# main.net
KiCad netlist of a schematic drawn in EAGLE
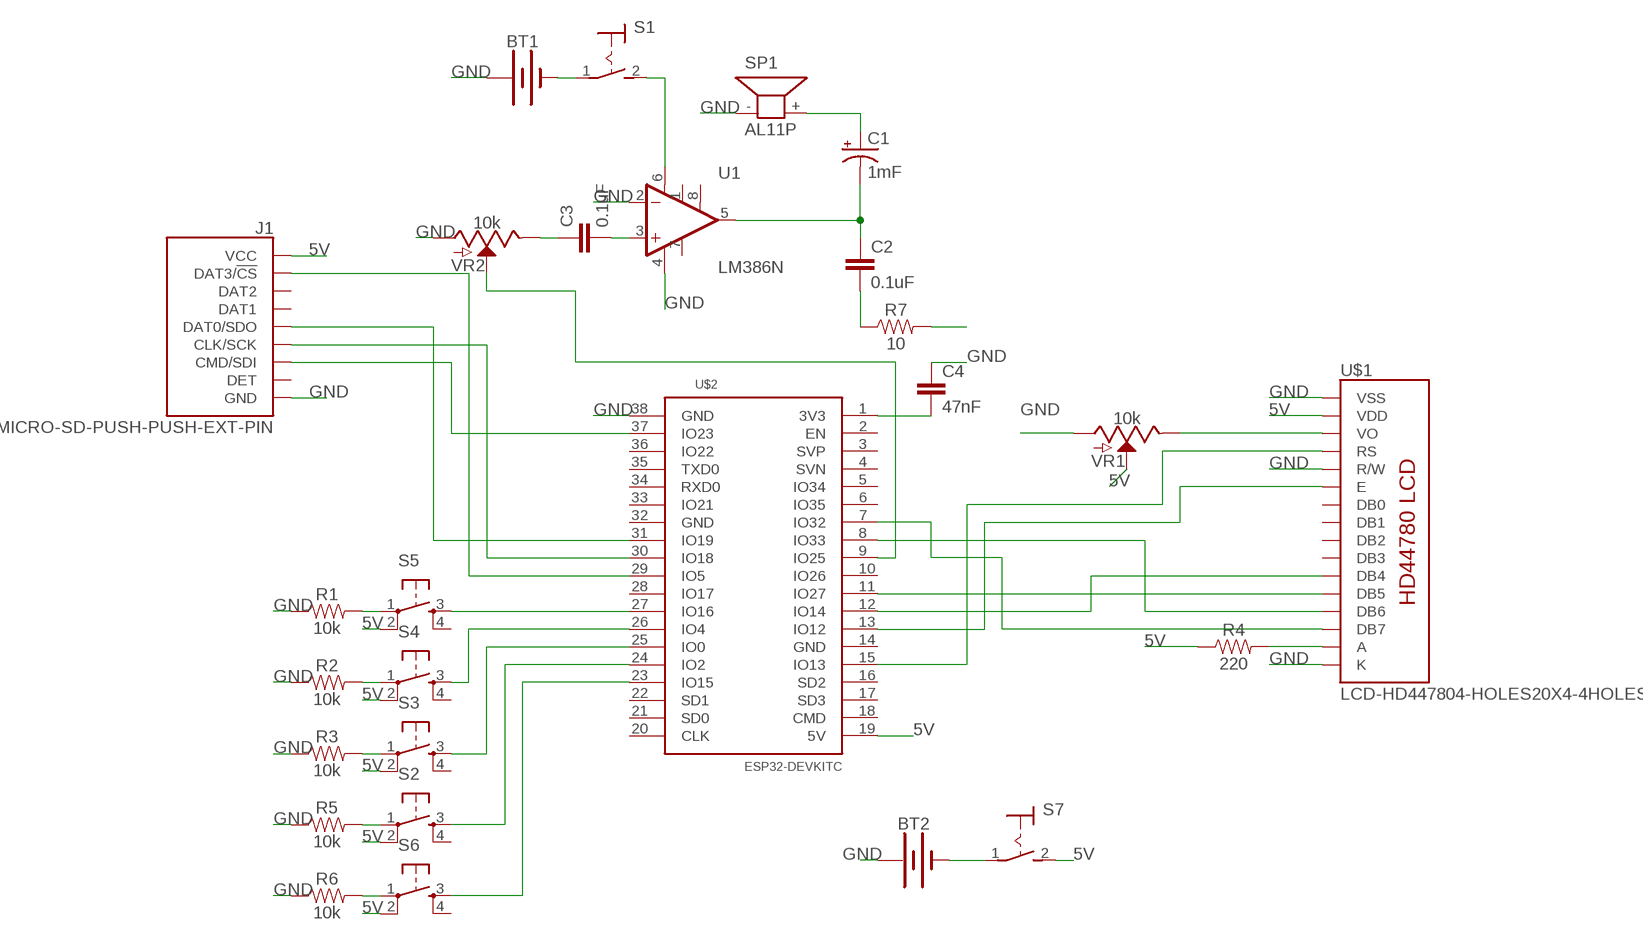
[diagram p0: schematic, sheet 1]

(export (version "E")
  (design (tool "Eeschema 10.0.6"))
  (components
    (comp (ref "BT1")
      (value "BATTERY-9V")
      (footprint "eagle-import:BATTCON_9V")
      (libsource (lib "eagle-import") (part "BATTERY-9V"))
    )
    (comp (ref "BT2")
      (value "BATTERY-9V")
      (footprint "eagle-import:BATTCON_9V")
      (libsource (lib "eagle-import") (part "BATTERY-9V"))
    )
    (comp (ref "C1")
      (value "1mF")
      (footprint "eagle-import:CPOL-RADIAL-5MM-10MM")
      (libsource (lib "eagle-import") (part "1000UF-RADIAL-5MM-25V-20%"))
    )
    (comp (ref "C2")
      (value "0.1uF")
      (footprint "eagle-import:CAP-PTH-SMALL-KIT")
      (libsource (lib "eagle-import") (part "0.1UF-KIT-EZ-50V-20%"))
    )
    (comp (ref "C3")
      (value "0.1uF")
      (footprint "eagle-import:CAP-PTH-SMALL-KIT")
      (libsource (lib "eagle-import") (part "0.1UF-KIT-EZ-50V-20%"))
    )
    (comp (ref "C4")
      (value "47nF")
      (footprint "eagle-import:0603")
      (libsource (lib "eagle-import") (part "47NF-0603-25V-5%"))
    )
    (comp (ref "J1")
      (value "MICRO-SD-PUSH-PUSH-EXT-PIN")
      (footprint "eagle-import:MICROSD-EXTERNALPIN")
      (libsource (lib "eagle-import") (part "MICRO-SD-PUSH-PUSH-EXT-PIN"))
    )
    (comp (ref "R1")
      (value "10k")
      (footprint "eagle-import:AXIAL-0.3")
      (libsource (lib "eagle-import") (part "10KOHM-HORIZ-1/4W-1%"))
    )
    (comp (ref "R2")
      (value "10k")
      (footprint "eagle-import:AXIAL-0.3")
      (libsource (lib "eagle-import") (part "10KOHM-HORIZ-1/4W-1%"))
    )
    (comp (ref "R3")
      (value "10k")
      (footprint "eagle-import:AXIAL-0.3")
      (libsource (lib "eagle-import") (part "10KOHM-HORIZ-1/4W-1%"))
    )
    (comp (ref "R4")
      (value "220")
      (footprint "eagle-import:0603")
      (libsource (lib "eagle-import") (part "220OHM-0603-1/10W-1%"))
    )
    (comp (ref "R5")
      (value "10k")
      (footprint "eagle-import:AXIAL-0.3")
      (libsource (lib "eagle-import") (part "10KOHM-HORIZ-1/4W-1%"))
    )
    (comp (ref "R6")
      (value "10k")
      (footprint "eagle-import:AXIAL-0.3")
      (libsource (lib "eagle-import") (part "10KOHM-HORIZ-1/4W-1%"))
    )
    (comp (ref "R7")
      (value "10")
      (footprint "eagle-import:AXIAL-0.3")
      (libsource (lib "eagle-import") (part "10OHM-HORIZ-1/4W-1%"))
    )
    (comp (ref "S1")
      (value "MS243")
      (footprint "eagle-import:MS243")
      (libsource (lib "eagle-import") (part "MS243"))
    )
    (comp (ref "S2")
      (value "TAC_SWITCHPTH")
      (footprint "eagle-import:TACTILE-PTH")
      (fields (field (name "SPICEPREFIX") "S"))
      (libsource (lib "eagle-import") (part "TAC_SWITCHPTH"))
    )
    (comp (ref "S3")
      (value "TAC_SWITCHPTH")
      (footprint "eagle-import:TACTILE-PTH")
      (fields (field (name "SPICEPREFIX") "S"))
      (libsource (lib "eagle-import") (part "TAC_SWITCHPTH"))
    )
    (comp (ref "S4")
      (value "TAC_SWITCHPTH")
      (footprint "eagle-import:TACTILE-PTH")
      (fields (field (name "SPICEPREFIX") "S"))
      (libsource (lib "eagle-import") (part "TAC_SWITCHPTH"))
    )
    (comp (ref "S5")
      (value "TAC_SWITCHPTH")
      (footprint "eagle-import:TACTILE-PTH")
      (fields (field (name "SPICEPREFIX") "S"))
      (libsource (lib "eagle-import") (part "TAC_SWITCHPTH"))
    )
    (comp (ref "S6")
      (value "TAC_SWITCHPTH")
      (footprint "eagle-import:TACTILE-PTH")
      (fields (field (name "SPICEPREFIX") "S"))
      (libsource (lib "eagle-import") (part "TAC_SWITCHPTH"))
    )
    (comp (ref "S7")
      (value "MS243")
      (footprint "eagle-import:MS243")
      (libsource (lib "eagle-import") (part "MS243"))
    )
    (comp (ref "SP1")
      (value "AL11P")
      (footprint "eagle-import:AL11P")
      (libsource (lib "eagle-import") (part "AL11P"))
    )
    (comp (ref "U$1")
      (value "LCD-HD447804-HOLES20X4-4HOLES")
      (footprint "eagle-import:LCD-20X4-4HOLES")
      (libsource (lib "eagle-import") (part "LCD-HD4478020X4-4HOLES4-HOLES"))
    )
    (comp (ref "U$2")
      (value "ESP32DEVKITC")
      (footprint "eagle-import:ESP32-DEVKITC")
      (libsource (lib "eagle-import") (part "ESP32DEVKITC"))
    )
    (comp (ref "U1")
      (value "LM386N")
      (footprint "eagle-import:DIP08")
      (libsource (lib "eagle-import") (part "LM386"))
    )
    (comp (ref "VR1")
      (value "10k")
      (footprint "eagle-import:SLIDER-XLARGE")
      (libsource (lib "eagle-import") (part "POTENTIOMETER_SLIDE-60MM-1/2W-20%"))
    )
    (comp (ref "VR2")
      (value "10k")
      (footprint "eagle-import:SLIDER-XLARGE")
      (libsource (lib "eagle-import") (part "POTENTIOMETER_SLIDE-60MM-1/2W-20%"))
    )
  )
  (nets
    (net (code "1") (name "/5V") (class "Default")
      (node (ref "J1") (pin "4") (pinfunction "VCC_4") (pintype "bidirectional"))
      (node (ref "R4") (pin "1") (pinfunction "1_1") (pintype "passive"))
      (node (ref "S2") (pin "2") (pinfunction "2_2") (pintype "passive"))
      (node (ref "S3") (pin "2") (pinfunction "2_2") (pintype "passive"))
      (node (ref "S4") (pin "2") (pinfunction "2_2") (pintype "passive"))
      (node (ref "S5") (pin "2") (pinfunction "2_2") (pintype "passive"))
      (node (ref "S6") (pin "2") (pinfunction "2_2") (pintype "passive"))
      (node (ref "S7") (pin "2") (pinfunction "S_2") (pintype "passive"))
      (node (ref "U$1") (pin "P$2") (pinfunction "VDD_P$2") (pintype "power_in"))
      (node (ref "U$2") (pin "19") (pinfunction "5V_19") (pintype "bidirectional"))
      (node (ref "VR1") (pin "2A") (pinfunction "S_2A") (pintype "passive"))
    )
    (net (code "2") (name "/GND") (class "Default")
      (node (ref "BT1") (pin "+") (pinfunction "+_+") (pintype "power_in"))
      (node (ref "BT2") (pin "+") (pinfunction "+_+") (pintype "power_in"))
      (node (ref "C4") (pin "1") (pinfunction "1_1") (pintype "passive"))
      (node (ref "J1") (pin "10") (pinfunction "GND_10") (pintype "bidirectional"))
      (node (ref "J1") (pin "11") (pinfunction "GND_11") (pintype "bidirectional"))
      (node (ref "J1") (pin "12") (pinfunction "GND_12") (pintype "bidirectional"))
      (node (ref "J1") (pin "13") (pinfunction "GND_13") (pintype "bidirectional"))
      (node (ref "J1") (pin "6") (pinfunction "GND_6") (pintype "bidirectional"))
      (node (ref "R1") (pin "P$1") (pinfunction "1_P$1") (pintype "passive"))
      (node (ref "R2") (pin "P$1") (pinfunction "1_P$1") (pintype "passive"))
      (node (ref "R3") (pin "P$1") (pinfunction "1_P$1") (pintype "passive"))
      (node (ref "R5") (pin "P$1") (pinfunction "1_P$1") (pintype "passive"))
      (node (ref "R6") (pin "P$1") (pinfunction "1_P$1") (pintype "passive"))
      (node (ref "SP1") (pin "-") (pinfunction "1_-") (pintype "passive"))
      (node (ref "U$1") (pin "P$1") (pinfunction "VSS_P$1") (pintype "power_in"))
      (node (ref "U$1") (pin "P$16") (pinfunction "K_P$16") (pintype "power_in"))
      (node (ref "U$1") (pin "P$5") (pinfunction "R/W_P$5") (pintype "input"))
      (node (ref "U$2") (pin "38") (pinfunction "GND_38") (pintype "bidirectional"))
      (node (ref "U1") (pin "2") (pinfunction "-IN_2") (pintype "input"))
      (node (ref "U1") (pin "4") (pinfunction "V-_4") (pintype "power_in"))
      (node (ref "VR1") (pin "3") (pinfunction "A_3") (pintype "passive"))
      (node (ref "VR2") (pin "3") (pinfunction "A_3") (pintype "passive"))
    )
    (net (code "3") (name "Net-(J1-CLK{slash}SCK)") (class "Default")
      (node (ref "J1") (pin "5") (pinfunction "CLK/SCK_5") (pintype "bidirectional"))
      (node (ref "U$2") (pin "30") (pinfunction "IO18_30") (pintype "bidirectional"))
    )
    (net (code "4") (name "Net-(J1-CMD{slash}SDI)") (class "Default")
      (node (ref "J1") (pin "3") (pinfunction "CMD/SDI_3") (pintype "bidirectional"))
      (node (ref "U$2") (pin "37") (pinfunction "IO23_37") (pintype "bidirectional"))
    )
    (net (code "5") (name "Net-(J1-DAT0{slash}SDO)") (class "Default")
      (node (ref "J1") (pin "7") (pinfunction "DAT0/SDO_7") (pintype "bidirectional"))
      (node (ref "U$2") (pin "31") (pinfunction "IO19_31") (pintype "bidirectional"))
    )
    (net (code "6") (name "Net-(J1-DAT3{slash}~{CS})") (class "Default")
      (node (ref "J1") (pin "2") (pinfunction "DAT3/~{CS}_2") (pintype "bidirectional"))
      (node (ref "U$2") (pin "29") (pinfunction "IO5_29") (pintype "bidirectional"))
    )
    (net (code "7") (name "Net-(R1-2)") (class "Default")
      (node (ref "R1") (pin "P$2") (pinfunction "2_P$2") (pintype "passive"))
      (node (ref "S5") (pin "1") (pinfunction "1_1") (pintype "passive"))
    )
    (net (code "8") (name "Net-(R2-2)") (class "Default")
      (node (ref "R2") (pin "P$2") (pinfunction "2_P$2") (pintype "passive"))
      (node (ref "S4") (pin "1") (pinfunction "1_1") (pintype "passive"))
    )
    (net (code "9") (name "Net-(R3-2)") (class "Default")
      (node (ref "R3") (pin "P$2") (pinfunction "2_P$2") (pintype "passive"))
      (node (ref "S3") (pin "1") (pinfunction "1_1") (pintype "passive"))
    )
    (net (code "10") (name "Net-(R5-2)") (class "Default")
      (node (ref "R5") (pin "P$2") (pinfunction "2_P$2") (pintype "passive"))
      (node (ref "S2") (pin "1") (pinfunction "1_1") (pintype "passive"))
    )
    (net (code "11") (name "Net-(R6-2)") (class "Default")
      (node (ref "R6") (pin "P$2") (pinfunction "2_P$2") (pintype "passive"))
      (node (ref "S6") (pin "1") (pinfunction "1_1") (pintype "passive"))
    )
    (net (code "12") (name "Net-(R7-1)") (class "Default")
      (node (ref "C2") (pin "2") (pinfunction "2_2") (pintype "passive"))
      (node (ref "R7") (pin "P$1") (pinfunction "1_P$1") (pintype "passive"))
    )
    (net (code "13") (name "Net-(S1-P)") (class "Default")
      (node (ref "BT1") (pin "-") (pinfunction "-_-") (pintype "power_in"))
      (node (ref "S1") (pin "1") (pinfunction "P_1") (pintype "passive"))
    )
    (net (code "14") (name "Net-(S1-S)") (class "Default")
      (node (ref "S1") (pin "2") (pinfunction "S_2") (pintype "passive"))
      (node (ref "U1") (pin "6") (pinfunction "V+_6") (pintype "power_in"))
    )
    (net (code "15") (name "Net-(S7-P)") (class "Default")
      (node (ref "BT2") (pin "-") (pinfunction "-_-") (pintype "power_in"))
      (node (ref "S7") (pin "1") (pinfunction "P_1") (pintype "passive"))
    )
    (net (code "16") (name "Net-(SP1-2)") (class "Default")
      (node (ref "C1") (pin "+") (pinfunction "+_+") (pintype "passive"))
      (node (ref "SP1") (pin "+") (pinfunction "2_+") (pintype "passive"))
    )
    (net (code "17") (name "Net-(U$1-A)") (class "Default")
      (node (ref "R4") (pin "2") (pinfunction "2_2") (pintype "passive"))
      (node (ref "U$1") (pin "P$15") (pinfunction "A_P$15") (pintype "power_in"))
    )
    (net (code "18") (name "Net-(U$1-DB4)") (class "Default")
      (node (ref "U$1") (pin "P$11") (pinfunction "DB4_P$11") (pintype "bidirectional"))
      (node (ref "U$2") (pin "12") (pinfunction "IO14_12") (pintype "bidirectional"))
    )
    (net (code "19") (name "Net-(U$1-DB5)") (class "Default")
      (node (ref "U$1") (pin "P$12") (pinfunction "DB5_P$12") (pintype "bidirectional"))
      (node (ref "U$2") (pin "11") (pinfunction "IO27_11") (pintype "bidirectional"))
    )
    (net (code "20") (name "Net-(U$1-DB6)") (class "Default")
      (node (ref "U$1") (pin "P$13") (pinfunction "DB6_P$13") (pintype "bidirectional"))
      (node (ref "U$2") (pin "8") (pinfunction "IO33_8") (pintype "bidirectional"))
    )
    (net (code "21") (name "Net-(U$1-DB7)") (class "Default")
      (node (ref "U$1") (pin "P$14") (pinfunction "DB7_P$14") (pintype "bidirectional"))
      (node (ref "U$2") (pin "7") (pinfunction "IO32_7") (pintype "bidirectional"))
    )
    (net (code "22") (name "Net-(U$1-E)") (class "Default")
      (node (ref "U$1") (pin "P$6") (pinfunction "E_P$6") (pintype "input"))
      (node (ref "U$2") (pin "13") (pinfunction "IO12_13") (pintype "bidirectional"))
    )
    (net (code "23") (name "Net-(U$1-RS)") (class "Default")
      (node (ref "U$1") (pin "P$4") (pinfunction "RS_P$4") (pintype "input"))
      (node (ref "U$2") (pin "15") (pinfunction "IO13_15") (pintype "bidirectional"))
    )
    (net (code "24") (name "Net-(U$1-VO)") (class "Default")
      (node (ref "U$1") (pin "P$3") (pinfunction "VO_P$3") (pintype "bidirectional"))
      (node (ref "VR1") (pin "1") (pinfunction "E_1") (pintype "passive"))
    )
    (net (code "25") (name "Net-(U$2-3V3)") (class "Default")
      (node (ref "C4") (pin "2") (pinfunction "2_2") (pintype "passive"))
      (node (ref "U$2") (pin "1") (pinfunction "3V3_1") (pintype "bidirectional"))
    )
    (net (code "26") (name "Net-(U$2-IO0)") (class "Default")
      (node (ref "S3") (pin "3") (pinfunction "3_3") (pintype "passive"))
      (node (ref "U$2") (pin "25") (pinfunction "IO0_25") (pintype "bidirectional"))
    )
    (net (code "27") (name "Net-(U$2-IO2)") (class "Default")
      (node (ref "S2") (pin "3") (pinfunction "3_3") (pintype "passive"))
      (node (ref "U$2") (pin "24") (pinfunction "IO2_24") (pintype "bidirectional"))
    )
    (net (code "28") (name "Net-(U$2-IO4)") (class "Default")
      (node (ref "S4") (pin "3") (pinfunction "3_3") (pintype "passive"))
      (node (ref "U$2") (pin "26") (pinfunction "IO4_26") (pintype "bidirectional"))
    )
    (net (code "29") (name "Net-(U$2-IO15)") (class "Default")
      (node (ref "S6") (pin "3") (pinfunction "3_3") (pintype "passive"))
      (node (ref "U$2") (pin "23") (pinfunction "IO15_23") (pintype "bidirectional"))
    )
    (net (code "30") (name "Net-(U$2-IO16)") (class "Default")
      (node (ref "S5") (pin "3") (pinfunction "3_3") (pintype "passive"))
      (node (ref "U$2") (pin "27") (pinfunction "IO16_27") (pintype "bidirectional"))
    )
    (net (code "31") (name "Net-(U$2-IO25)") (class "Default")
      (node (ref "U$2") (pin "9") (pinfunction "IO25_9") (pintype "bidirectional"))
      (node (ref "VR2") (pin "2A") (pinfunction "S_2A") (pintype "passive"))
    )
    (net (code "32") (name "Net-(U1-+IN)") (class "Default")
      (node (ref "C3") (pin "2") (pinfunction "2_2") (pintype "passive"))
      (node (ref "U1") (pin "3") (pinfunction "+IN_3") (pintype "input"))
    )
    (net (code "33") (name "Net-(U1-OUT)") (class "Default")
      (node (ref "C1") (pin "-") (pinfunction "-_-") (pintype "passive"))
      (node (ref "C2") (pin "1") (pinfunction "1_1") (pintype "passive"))
      (node (ref "U1") (pin "5") (pinfunction "OUT_5") (pintype "output"))
    )
    (net (code "34") (name "Net-(VR2-E)") (class "Default")
      (node (ref "C3") (pin "1") (pinfunction "1_1") (pintype "passive"))
      (node (ref "VR2") (pin "1") (pinfunction "E_1") (pintype "passive"))
    )
    (net (code "35") (name "unconnected-(J1-DAT1-Pad8)") (class "Default")
      (node (ref "J1") (pin "8") (pinfunction "DAT1_8") (pintype "bidirectional"))
    )
    (net (code "36") (name "unconnected-(J1-DAT2-Pad1)") (class "Default")
      (node (ref "J1") (pin "1") (pinfunction "DAT2_1") (pintype "bidirectional"))
    )
    (net (code "37") (name "unconnected-(J1-DET-Pad9)") (class "Default")
      (node (ref "J1") (pin "9") (pinfunction "DET_9") (pintype "bidirectional"))
    )
    (net (code "38") (name "unconnected-(R7-2-PadP$2)") (class "Default")
      (node (ref "R7") (pin "P$2") (pinfunction "2_P$2") (pintype "passive"))
    )
    (net (code "39") (name "unconnected-(S2-Pad4)") (class "Default")
      (node (ref "S2") (pin "4") (pinfunction "4_4") (pintype "passive"))
    )
    (net (code "40") (name "unconnected-(S3-Pad4)") (class "Default")
      (node (ref "S3") (pin "4") (pinfunction "4_4") (pintype "passive"))
    )
    (net (code "41") (name "unconnected-(S4-Pad4)") (class "Default")
      (node (ref "S4") (pin "4") (pinfunction "4_4") (pintype "passive"))
    )
    (net (code "42") (name "unconnected-(S5-Pad4)") (class "Default")
      (node (ref "S5") (pin "4") (pinfunction "4_4") (pintype "passive"))
    )
    (net (code "43") (name "unconnected-(S6-Pad4)") (class "Default")
      (node (ref "S6") (pin "4") (pinfunction "4_4") (pintype "passive"))
    )
    (net (code "44") (name "unconnected-(U$1-DB0-PadP$7)") (class "Default")
      (node (ref "U$1") (pin "P$7") (pinfunction "DB0_P$7") (pintype "bidirectional"))
    )
    (net (code "45") (name "unconnected-(U$1-DB1-PadP$8)") (class "Default")
      (node (ref "U$1") (pin "P$8") (pinfunction "DB1_P$8") (pintype "bidirectional"))
    )
    (net (code "46") (name "unconnected-(U$1-DB2-PadP$9)") (class "Default")
      (node (ref "U$1") (pin "P$9") (pinfunction "DB2_P$9") (pintype "bidirectional"))
    )
    (net (code "47") (name "unconnected-(U$1-DB3-PadP$10)") (class "Default")
      (node (ref "U$1") (pin "P$10") (pinfunction "DB3_P$10") (pintype "bidirectional"))
    )
    (net (code "48") (name "unconnected-(U$2-CLK-Pad20)") (class "Default")
      (node (ref "U$2") (pin "20") (pinfunction "CLK_20") (pintype "bidirectional"))
    )
    (net (code "49") (name "unconnected-(U$2-CMD-Pad18)") (class "Default")
      (node (ref "U$2") (pin "18") (pinfunction "CMD_18") (pintype "bidirectional"))
    )
    (net (code "50") (name "unconnected-(U$2-EN-Pad2)") (class "Default")
      (node (ref "U$2") (pin "2") (pinfunction "EN_2") (pintype "bidirectional"))
    )
    (net (code "51") (name "unconnected-(U$2-GND-Pad14)") (class "Default")
      (node (ref "U$2") (pin "14") (pinfunction "GND_14") (pintype "bidirectional"))
    )
    (net (code "52") (name "unconnected-(U$2-GND-Pad32)") (class "Default")
      (node (ref "U$2") (pin "32") (pinfunction "GND_32") (pintype "bidirectional"))
    )
    (net (code "53") (name "unconnected-(U$2-IO17-Pad28)") (class "Default")
      (node (ref "U$2") (pin "28") (pinfunction "IO17_28") (pintype "bidirectional"))
    )
    (net (code "54") (name "unconnected-(U$2-IO21-Pad33)") (class "Default")
      (node (ref "U$2") (pin "33") (pinfunction "IO21_33") (pintype "bidirectional"))
    )
    (net (code "55") (name "unconnected-(U$2-IO22-Pad36)") (class "Default")
      (node (ref "U$2") (pin "36") (pinfunction "IO22_36") (pintype "bidirectional"))
    )
    (net (code "56") (name "unconnected-(U$2-IO26-Pad10)") (class "Default")
      (node (ref "U$2") (pin "10") (pinfunction "IO26_10") (pintype "bidirectional"))
    )
    (net (code "57") (name "unconnected-(U$2-IO34-Pad5)") (class "Default")
      (node (ref "U$2") (pin "5") (pinfunction "IO34_5") (pintype "bidirectional"))
    )
    (net (code "58") (name "unconnected-(U$2-IO35-Pad6)") (class "Default")
      (node (ref "U$2") (pin "6") (pinfunction "IO35_6") (pintype "bidirectional"))
    )
    (net (code "59") (name "unconnected-(U$2-RXD0-Pad34)") (class "Default")
      (node (ref "U$2") (pin "34") (pinfunction "RXD0_34") (pintype "bidirectional"))
    )
    (net (code "60") (name "unconnected-(U$2-SD0-Pad21)") (class "Default")
      (node (ref "U$2") (pin "21") (pinfunction "SD0_21") (pintype "bidirectional"))
    )
    (net (code "61") (name "unconnected-(U$2-SD1-Pad22)") (class "Default")
      (node (ref "U$2") (pin "22") (pinfunction "SD1_22") (pintype "bidirectional"))
    )
    (net (code "62") (name "unconnected-(U$2-SD2-Pad16)") (class "Default")
      (node (ref "U$2") (pin "16") (pinfunction "SD2_16") (pintype "bidirectional"))
    )
    (net (code "63") (name "unconnected-(U$2-SD3-Pad17)") (class "Default")
      (node (ref "U$2") (pin "17") (pinfunction "SD3_17") (pintype "bidirectional"))
    )
    (net (code "64") (name "unconnected-(U$2-SVN-Pad4)") (class "Default")
      (node (ref "U$2") (pin "4") (pinfunction "SVN_4") (pintype "bidirectional"))
    )
    (net (code "65") (name "unconnected-(U$2-SVP-Pad3)") (class "Default")
      (node (ref "U$2") (pin "3") (pinfunction "SVP_3") (pintype "bidirectional"))
    )
    (net (code "66") (name "unconnected-(U$2-TXD0-Pad35)") (class "Default")
      (node (ref "U$2") (pin "35") (pinfunction "TXD0_35") (pintype "bidirectional"))
    )
    (net (code "67") (name "unconnected-(U1-BP-Pad7)") (class "Default")
      (node (ref "U1") (pin "7") (pinfunction "BP_7") (pintype "bidirectional"))
    )
    (net (code "68") (name "unconnected-(U1-GAIN-Pad1)") (class "Default")
      (node (ref "U1") (pin "1") (pinfunction "GAIN_1") (pintype "bidirectional"))
    )
    (net (code "69") (name "unconnected-(U1-GAIN-Pad8)") (class "Default")
      (node (ref "U1") (pin "8") (pinfunction "GAIN_8") (pintype "bidirectional"))
    )
  )
)
